# FTDI_board.net
KiCad netlist of a schematic drawn in EAGLE
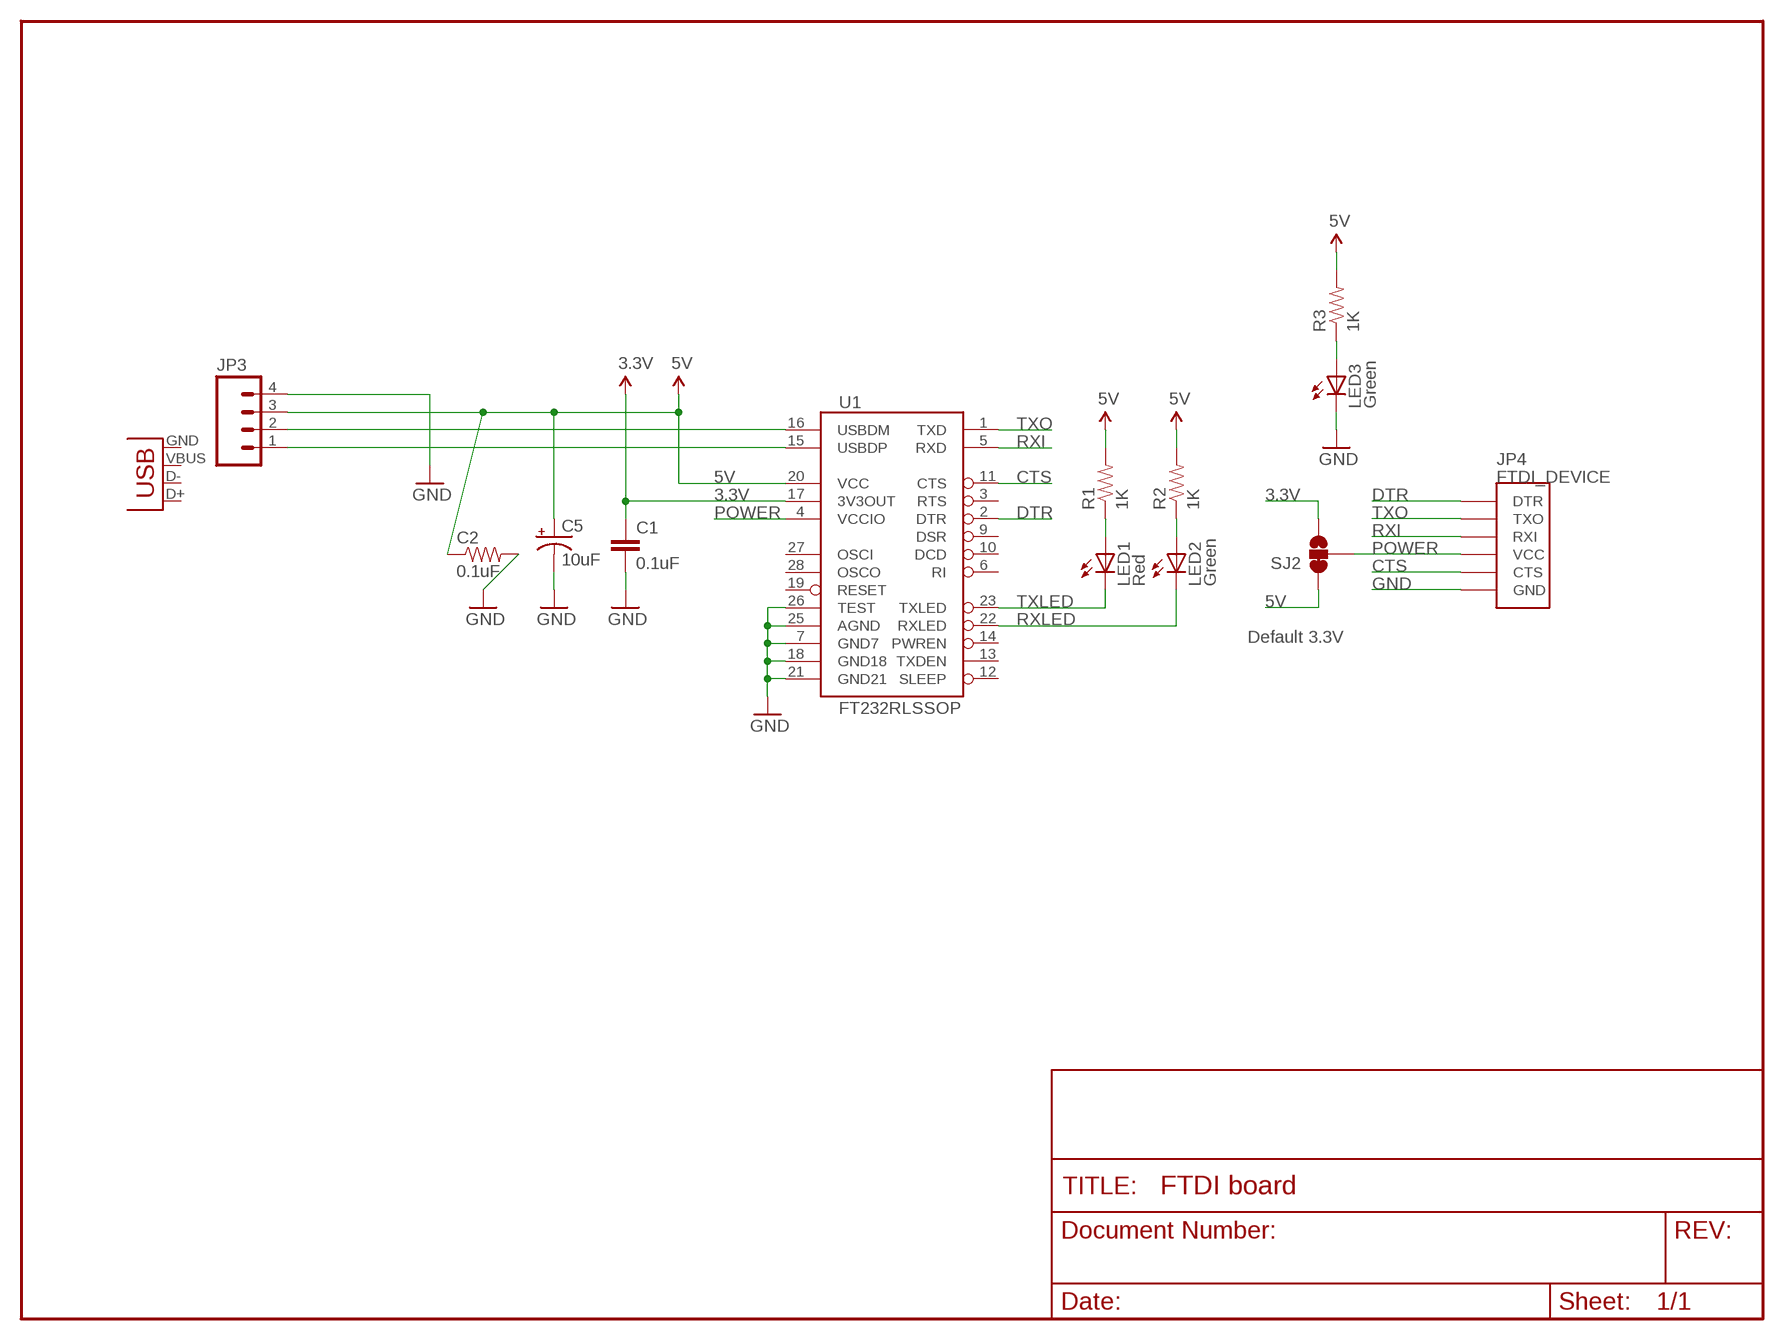
[diagram p0: schematic, sheet 1]

(export (version "E")
  (design (tool "Eeschema 10.0.6"))
  (components
    (comp (ref "C1")
      (value "0.1uF")
      (footprint "eagle-import:0402-CAP")
      (libsource (lib "eagle-import") (part "CAP0402-CAP"))
    )
    (comp (ref "C2")
      (value "0.1uF")
      (footprint "eagle-import:AXIAL-0.1")
      (libsource (lib "eagle-import") (part "RESISTORPTH-1/4W-VERT"))
    )
    (comp (ref "C5")
      (value "10uF")
      (footprint "eagle-import:EIA3216")
      (libsource (lib "eagle-import") (part "CAP_POL1206"))
    )
    (comp (ref "JP3")
      (value "M04LOCK")
      (footprint "eagle-import:1X04_LOCK")
      (libsource (lib "eagle-import") (part "M04LOCK"))
    )
    (comp (ref "JP4")
      (value "FTDI_DEVICE")
      (footprint "eagle-import:FTDI_DEVICE_SIDE")
      (libsource (lib "eagle-import") (part "FTDI_DEVICE"))
    )
    (comp (ref "LED1")
      (value "Red")
      (footprint "eagle-import:LED5MM")
      (libsource (lib "eagle-import") (part "LED5MM"))
    )
    (comp (ref "LED2")
      (value "Green")
      (footprint "eagle-import:LED5MM")
      (libsource (lib "eagle-import") (part "LED5MM"))
    )
    (comp (ref "LED3")
      (value "Green")
      (footprint "eagle-import:LED5MM")
      (libsource (lib "eagle-import") (part "LED5MM"))
    )
    (comp (ref "R1")
      (value "1K")
      (footprint "eagle-import:AXIAL-0.1")
      (libsource (lib "eagle-import") (part "RESISTORPTH-1/4W-VERT"))
    )
    (comp (ref "R2")
      (value "1K")
      (footprint "eagle-import:AXIAL-0.1")
      (libsource (lib "eagle-import") (part "RESISTORPTH-1/4W-VERT"))
    )
    (comp (ref "R3")
      (value "1K")
      (footprint "eagle-import:AXIAL-0.1")
      (libsource (lib "eagle-import") (part "RESISTORPTH-1/4W-VERT"))
    )
    (comp (ref "SJ2")
      (value "SOLDERJUMPER_2WAYS")
      (footprint "eagle-import:SJ_3")
      (libsource (lib "eagle-import") (part "SOLDERJUMPER_2WAYS"))
    )
    (comp (ref "U1")
      (value "FT232RLSSOP")
      (footprint "eagle-import:SSOP28DB")
      (libsource (lib "eagle-import") (part "FT232RLSSOP"))
    )
    (comp (ref "X1")
      (value "USB-SMD-NS")
      (footprint "eagle-import:USB-MINIB-NOSTOP")
      (libsource (lib "eagle-import") (part "USB-SMD-NS"))
    )
  )
  (nets
    (net (code "1") (name "/CTS") (class "Default")
      (node (ref "JP4") (pin "P$5") (pinfunction "CTS_P$5") (pintype "bidirectional"))
      (node (ref "U1") (pin "11") (pinfunction "CTS_11") (pintype "input"))
    )
    (net (code "2") (name "/DTR") (class "Default")
      (node (ref "JP4") (pin "P$1") (pinfunction "DTR_P$1") (pintype "bidirectional"))
      (node (ref "U1") (pin "2") (pinfunction "DTR_2") (pintype "output"))
    )
    (net (code "3") (name "/POWER") (class "Default")
      (node (ref "JP4") (pin "P$4") (pinfunction "VCC_P$4") (pintype "bidirectional"))
      (node (ref "SJ2") (pin "2") (pinfunction "2_2") (pintype "passive"))
      (node (ref "U1") (pin "4") (pinfunction "VCCIO_4") (pintype "power_in"))
    )
    (net (code "4") (name "/RXI") (class "Default")
      (node (ref "JP4") (pin "P$3") (pinfunction "RXI_P$3") (pintype "bidirectional"))
      (node (ref "U1") (pin "5") (pinfunction "RXD_5") (pintype "input"))
    )
    (net (code "5") (name "/RXLED") (class "Default")
      (node (ref "LED2") (pin "K") (pinfunction "C_K") (pintype "passive"))
      (node (ref "U1") (pin "22") (pinfunction "RXLED_22") (pintype "input"))
    )
    (net (code "6") (name "/TXLED") (class "Default")
      (node (ref "LED1") (pin "K") (pinfunction "C_K") (pintype "passive"))
      (node (ref "U1") (pin "23") (pinfunction "TXLED_23") (pintype "input"))
    )
    (net (code "7") (name "/TXO") (class "Default")
      (node (ref "JP4") (pin "P$2") (pinfunction "TXO_P$2") (pintype "bidirectional"))
      (node (ref "U1") (pin "1") (pinfunction "TXD_1") (pintype "output"))
    )
    (net (code "8") (name "3.3V") (class "Default")
      (node (ref "C1") (pin "1") (pinfunction "1_1") (pintype "passive"))
      (node (ref "SJ2") (pin "3") (pinfunction "3_3") (pintype "passive"))
      (node (ref "U1") (pin "17") (pinfunction "3V3OUT_17") (pintype "output"))
    )
    (net (code "9") (name "5V") (class "Default")
      (node (ref "C2") (pin "P$1") (pinfunction "1_P$1") (pintype "passive"))
      (node (ref "C5") (pin "A") (pinfunction "+_A") (pintype "passive"))
      (node (ref "JP3") (pin "3") (pinfunction "3_3") (pintype "passive"))
      (node (ref "R1") (pin "P$2") (pinfunction "2_P$2") (pintype "passive"))
      (node (ref "R2") (pin "P$2") (pinfunction "2_P$2") (pintype "passive"))
      (node (ref "R3") (pin "P$2") (pinfunction "2_P$2") (pintype "passive"))
      (node (ref "SJ2") (pin "1") (pinfunction "1_1") (pintype "passive"))
      (node (ref "U1") (pin "20") (pinfunction "VCC_20") (pintype "power_in"))
    )
    (net (code "10") (name "GND") (class "Default")
      (node (ref "C1") (pin "2") (pinfunction "2_2") (pintype "passive"))
      (node (ref "C2") (pin "P$2") (pinfunction "2_P$2") (pintype "passive"))
      (node (ref "C5") (pin "C") (pinfunction "-_C") (pintype "passive"))
      (node (ref "JP3") (pin "4") (pinfunction "4_4") (pintype "passive"))
      (node (ref "JP4") (pin "P$6") (pinfunction "GND_P$6") (pintype "bidirectional"))
      (node (ref "LED3") (pin "K") (pinfunction "C_K") (pintype "passive"))
      (node (ref "U1") (pin "18") (pinfunction "GND18_18") (pintype "power_in"))
      (node (ref "U1") (pin "21") (pinfunction "GND21_21") (pintype "power_in"))
      (node (ref "U1") (pin "25") (pinfunction "AGND_25") (pintype "power_in"))
      (node (ref "U1") (pin "26") (pinfunction "TEST_26") (pintype "input"))
      (node (ref "U1") (pin "7") (pinfunction "GND7_7") (pintype "power_in"))
    )
    (net (code "11") (name "Net-(R1-1)") (class "Default")
      (node (ref "LED1") (pin "A") (pinfunction "A_A") (pintype "passive"))
      (node (ref "R1") (pin "P$1") (pinfunction "1_P$1") (pintype "passive"))
    )
    (net (code "12") (name "Net-(R2-1)") (class "Default")
      (node (ref "LED2") (pin "A") (pinfunction "A_A") (pintype "passive"))
      (node (ref "R2") (pin "P$1") (pinfunction "1_P$1") (pintype "passive"))
    )
    (net (code "13") (name "Net-(R3-1)") (class "Default")
      (node (ref "LED3") (pin "A") (pinfunction "A_A") (pintype "passive"))
      (node (ref "R3") (pin "P$1") (pinfunction "1_P$1") (pintype "passive"))
    )
    (net (code "14") (name "Net-(U1-USBDM)") (class "Default")
      (node (ref "JP3") (pin "2") (pinfunction "2_2") (pintype "passive"))
      (node (ref "U1") (pin "16") (pinfunction "USBDM_16") (pintype "bidirectional"))
    )
    (net (code "15") (name "Net-(U1-USBDP)") (class "Default")
      (node (ref "JP3") (pin "1") (pinfunction "1_1") (pintype "passive"))
      (node (ref "U1") (pin "15") (pinfunction "USBDP_15") (pintype "bidirectional"))
    )
    (net (code "16") (name "unconnected-(U1-DCD-Pad10)") (class "Default")
      (node (ref "U1") (pin "10") (pinfunction "DCD_10") (pintype "input"))
    )
    (net (code "17") (name "unconnected-(U1-DSR-Pad9)") (class "Default")
      (node (ref "U1") (pin "9") (pinfunction "DSR_9") (pintype "input"))
    )
    (net (code "18") (name "unconnected-(U1-OSCI-Pad27)") (class "Default")
      (node (ref "U1") (pin "27") (pinfunction "OSCI_27") (pintype "input"))
    )
    (net (code "19") (name "unconnected-(U1-OSCO-Pad28)") (class "Default")
      (node (ref "U1") (pin "28") (pinfunction "OSCO_28") (pintype "output"))
    )
    (net (code "20") (name "unconnected-(U1-PWREN-Pad14)") (class "Default")
      (node (ref "U1") (pin "14") (pinfunction "PWREN_14") (pintype "input"))
    )
    (net (code "21") (name "unconnected-(U1-RESET-Pad19)") (class "Default")
      (node (ref "U1") (pin "19") (pinfunction "RESET_19") (pintype "input"))
    )
    (net (code "22") (name "unconnected-(U1-RI-Pad6)") (class "Default")
      (node (ref "U1") (pin "6") (pinfunction "RI_6") (pintype "input"))
    )
    (net (code "23") (name "unconnected-(U1-RTS-Pad3)") (class "Default")
      (node (ref "U1") (pin "3") (pinfunction "RTS_3") (pintype "output"))
    )
    (net (code "24") (name "unconnected-(U1-SLEEP-Pad12)") (class "Default")
      (node (ref "U1") (pin "12") (pinfunction "SLEEP_12") (pintype "input"))
    )
    (net (code "25") (name "unconnected-(U1-TXDEN-Pad13)") (class "Default")
      (node (ref "U1") (pin "13") (pinfunction "TXDEN_13") (pintype "input"))
    )
    (net (code "26") (name "unconnected-(X1-PadD+)") (class "Default")
      (node (ref "X1") (pin "D+") (pinfunction "D+_D+") (pintype "bidirectional"))
    )
    (net (code "27") (name "unconnected-(X1-PadD-)") (class "Default")
      (node (ref "X1") (pin "D-") (pinfunction "D-_D-") (pintype "bidirectional"))
    )
    (net (code "28") (name "unconnected-(X1-PadGND)") (class "Default")
      (node (ref "X1") (pin "GND") (pinfunction "GND_GND") (pintype "bidirectional"))
    )
    (net (code "29") (name "unconnected-(X1-PadVBUS)") (class "Default")
      (node (ref "X1") (pin "VBUS") (pinfunction "VBUS_VBUS") (pintype "bidirectional"))
    )
  )
)
